# rauch.net
KiCad netlist of a schematic drawn in Altium Designer
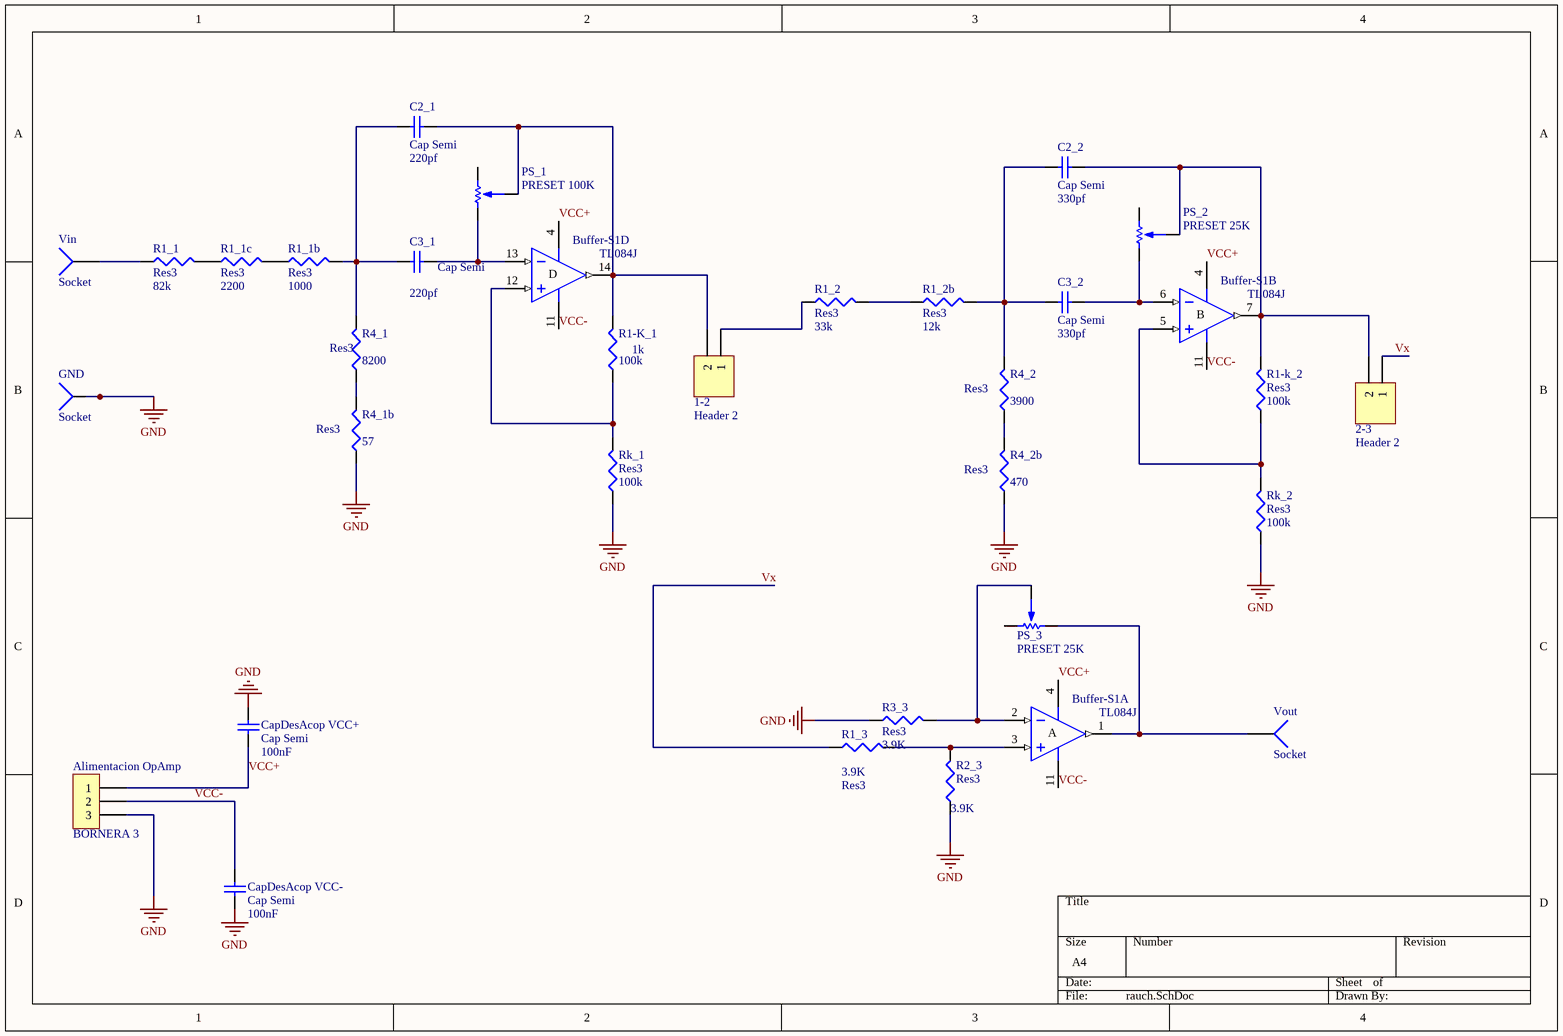
[diagram p0: rauch.SchDoc]

(export (version "E")
  (design (tool "Eeschema 10.0.6"))
  (components
    (comp (ref "1-2")
      (value "Header 2")
      (footprint "HDR1X2")
      (description "Header, 2-Pin")
      (fields (field (name "PUBLISHER") "Altium Limited"))
      (libsource (lib "Miscellaneous Connectors") (part "Header 2"))
    )
    (comp (ref "2-3")
      (value "Header 2")
      (footprint "HDR1X2")
      (description "Header, 2-Pin")
      (fields (field (name "PUBLISHER") "Altium Limited"))
      (libsource (lib "Miscellaneous Connectors") (part "Header 2"))
    )
    (comp (ref "Alimentacion OpAmp")
      (value "BORNERA 3")
      (footprint "BORNERA3")
      (libsource (lib "LIBEBAL") (part "BORNERA 3"))
    )
    (comp (ref "Buffer-S1")
      (value "TL084J")
      (footprint "J014")
      (description "JFET-Input Operational Amplifier")
      (fields (field (name "PUBLISHER") "Altium Limited"))
      (libsource (lib "TI Operational Amplifier") (part "TL084J"))
    )
    (comp (ref "C2_1")
      (value "Cap Semi")
      (footprint "C0805")
      (description "Capacitor (Semiconductor SIM Model)")
      (fields (field (name "ALTIUM_VALUE") "220pf") (field (name "PUBLISHER") "Altium Limited"))
      (libsource (lib "Miscellaneous Devices") (part "Cap Semi"))
    )
    (comp (ref "C2_2")
      (value "Cap Semi")
      (footprint "C0805")
      (description "Capacitor (Semiconductor SIM Model)")
      (fields (field (name "ALTIUM_VALUE") "330pf") (field (name "PUBLISHER") "Altium Limited"))
      (libsource (lib "Miscellaneous Devices") (part "Cap Semi"))
    )
    (comp (ref "C3_1")
      (value "Cap Semi")
      (footprint "C0805")
      (description "Capacitor (Semiconductor SIM Model)")
      (fields (field (name "ALTIUM_VALUE") "220pf") (field (name "PUBLISHER") "Altium Limited"))
      (libsource (lib "Miscellaneous Devices") (part "Cap Semi"))
    )
    (comp (ref "C3_2")
      (value "Cap Semi")
      (footprint "C0805")
      (description "Capacitor (Semiconductor SIM Model)")
      (fields (field (name "ALTIUM_VALUE") "330pf") (field (name "PUBLISHER") "Altium Limited"))
      (libsource (lib "Miscellaneous Devices") (part "Cap Semi"))
    )
    (comp (ref "CapDesAcop VCC+")
      (value "Cap Semi")
      (footprint "C0805")
      (description "Capacitor (Semiconductor SIM Model)")
      (fields (field (name "ALTIUM_VALUE") "100nF") (field (name "PUBLISHER") "Altium Limited"))
      (libsource (lib "Miscellaneous Devices") (part "Cap Semi"))
    )
    (comp (ref "CapDesAcop VCC-")
      (value "Cap Semi")
      (footprint "C0805")
      (description "Capacitor (Semiconductor SIM Model)")
      (fields (field (name "ALTIUM_VALUE") "100nF") (field (name "PUBLISHER") "Altium Limited"))
      (libsource (lib "Miscellaneous Devices") (part "Cap Semi"))
    )
    (comp (ref "GND")
      (value "Socket")
      (footprint "PIN1")
      (fields (field (name "PUBLISHER") "Altium Limited"))
      (libsource (lib "Miscellaneous Connectors") (part "Socket"))
    )
    (comp (ref "PS_1")
      (value "PRESET 100K")
      (footprint "PRESET V")
      (libsource (lib "LIBEBAL") (part "PRESET"))
    )
    (comp (ref "PS_2")
      (value "PRESET 25K")
      (footprint "PRESET V")
      (libsource (lib "LIBEBAL") (part "PRESET"))
    )
    (comp (ref "PS_3")
      (value "PRESET 25K")
      (footprint "PRESET V")
      (libsource (lib "LIBEBAL") (part "PRESET"))
    )
    (comp (ref "R1-K_1")
      (value "1k")
      (footprint "6-0805_M")
      (description "Resistor")
      (fields (field (name "ALTIUM_VALUE") "100k") (field (name "PUBLISHER") "Altium Limited"))
      (libsource (lib "Miscellaneous Devices") (part "Res3"))
    )
    (comp (ref "R1-k_2")
      (value "Res3")
      (footprint "6-0805_M")
      (description "Resistor")
      (fields (field (name "ALTIUM_VALUE") "100k") (field (name "PUBLISHER") "Altium Limited"))
      (libsource (lib "Miscellaneous Devices") (part "Res3"))
    )
    (comp (ref "R1_1")
      (value "Res3")
      (footprint "6-0805_M")
      (description "Resistor")
      (fields (field (name "ALTIUM_VALUE") "82k") (field (name "PUBLISHER") "Altium Limited"))
      (libsource (lib "Miscellaneous Devices") (part "Res3"))
    )
    (comp (ref "R1_1b")
      (value "Res3")
      (footprint "6-0805_M")
      (description "Resistor")
      (fields (field (name "ALTIUM_VALUE") "1000") (field (name "PUBLISHER") "Altium Limited"))
      (libsource (lib "Miscellaneous Devices") (part "Res3"))
    )
    (comp (ref "R1_1c")
      (value "Res3")
      (footprint "6-0805_M")
      (description "Resistor")
      (fields (field (name "ALTIUM_VALUE") "2200") (field (name "PUBLISHER") "Altium Limited"))
      (libsource (lib "Miscellaneous Devices") (part "Res3"))
    )
    (comp (ref "R1_2")
      (value "Res3")
      (footprint "6-0805_M")
      (description "Resistor")
      (fields (field (name "ALTIUM_VALUE") "33k") (field (name "PUBLISHER") "Altium Limited"))
      (libsource (lib "Miscellaneous Devices") (part "Res3"))
    )
    (comp (ref "R1_2b")
      (value "Res3")
      (footprint "6-0805_M")
      (description "Resistor")
      (fields (field (name "ALTIUM_VALUE") "12k") (field (name "PUBLISHER") "Altium Limited"))
      (libsource (lib "Miscellaneous Devices") (part "Res3"))
    )
    (comp (ref "R1_3")
      (value "Res3")
      (footprint "6-0805_M")
      (description "Resistor")
      (fields (field (name "ALTIUM_VALUE") "3.9K") (field (name "PUBLISHER") "Altium Limited"))
      (libsource (lib "Miscellaneous Devices") (part "Res3"))
    )
    (comp (ref "R2_3")
      (value "Res3")
      (footprint "6-0805_M")
      (description "Resistor")
      (fields (field (name "ALTIUM_VALUE") "3.9K") (field (name "PUBLISHER") "Altium Limited"))
      (libsource (lib "Miscellaneous Devices") (part "Res3"))
    )
    (comp (ref "R3_3")
      (value "Res3")
      (footprint "6-0805_M")
      (description "Resistor")
      (fields (field (name "ALTIUM_VALUE") "3.9K") (field (name "PUBLISHER") "Altium Limited"))
      (libsource (lib "Miscellaneous Devices") (part "Res3"))
    )
    (comp (ref "R4_1")
      (value "Res3")
      (footprint "6-0805_M")
      (description "Resistor")
      (fields (field (name "ALTIUM_VALUE") "8200") (field (name "PUBLISHER") "Altium Limited"))
      (libsource (lib "Miscellaneous Devices") (part "Res3"))
    )
    (comp (ref "R4_1b")
      (value "Res3")
      (footprint "6-0805_M")
      (description "Resistor")
      (fields (field (name "ALTIUM_VALUE") "57") (field (name "PUBLISHER") "Altium Limited"))
      (libsource (lib "Miscellaneous Devices") (part "Res3"))
    )
    (comp (ref "R4_2")
      (value "Res3")
      (footprint "6-0805_M")
      (description "Resistor")
      (fields (field (name "ALTIUM_VALUE") "3900") (field (name "PUBLISHER") "Altium Limited"))
      (libsource (lib "Miscellaneous Devices") (part "Res3"))
    )
    (comp (ref "R4_2b")
      (value "Res3")
      (footprint "6-0805_M")
      (description "Resistor")
      (fields (field (name "ALTIUM_VALUE") "470") (field (name "PUBLISHER") "Altium Limited"))
      (libsource (lib "Miscellaneous Devices") (part "Res3"))
    )
    (comp (ref "Rk_1")
      (value "Res3")
      (footprint "6-0805_M")
      (description "Resistor")
      (fields (field (name "ALTIUM_VALUE") "100k") (field (name "PUBLISHER") "Altium Limited"))
      (libsource (lib "Miscellaneous Devices") (part "Res3"))
    )
    (comp (ref "Rk_2")
      (value "Res3")
      (footprint "6-0805_M")
      (description "Resistor")
      (fields (field (name "ALTIUM_VALUE") "100k") (field (name "PUBLISHER") "Altium Limited"))
      (libsource (lib "Miscellaneous Devices") (part "Res3"))
    )
    (comp (ref "Vin")
      (value "Socket")
      (footprint "PIN1")
      (fields (field (name "PUBLISHER") "Altium Limited"))
      (libsource (lib "Miscellaneous Connectors") (part "Socket"))
    )
    (comp (ref "Vout")
      (value "Socket")
      (footprint "PIN1")
      (fields (field (name "PUBLISHER") "Altium Limited"))
      (libsource (lib "Miscellaneous Connectors") (part "Socket"))
    )
  )
  (nets
    (net (code "1") (name "/VCC+") (class "Default")
      (node (ref "Alimentacion OpAmp") (pin "1") (pinfunction "1_1") (pintype "passive"))
      (node (ref "Buffer-S1") (pin "4") (pinfunction "V+_4") (pintype "power_in"))
      (node (ref "CapDesAcop VCC+") (pin "2") (pinfunction "2_2") (pintype "passive"))
    )
    (net (code "2") (name "/VCC-") (class "Default")
      (node (ref "Alimentacion OpAmp") (pin "2") (pinfunction "2_2") (pintype "passive"))
      (node (ref "Buffer-S1") (pin "11") (pinfunction "V-_11") (pintype "power_in"))
      (node (ref "CapDesAcop VCC-") (pin "2") (pinfunction "2_2") (pintype "passive"))
    )
    (net (code "3") (name "/Vx") (class "Default")
      (node (ref "2-3") (pin "1") (pinfunction "1_1") (pintype "passive"))
      (node (ref "R1_3") (pin "1") (pinfunction "1_1") (pintype "passive"))
    )
    (net (code "4") (name "GND") (class "Default")
      (node (ref "Alimentacion OpAmp") (pin "3") (pinfunction "3_3") (pintype "passive"))
      (node (ref "CapDesAcop VCC+") (pin "1") (pinfunction "1_1") (pintype "passive"))
      (node (ref "CapDesAcop VCC-") (pin "1") (pinfunction "1_1") (pintype "passive"))
      (node (ref "GND") (pin "1") (pinfunction "1_1") (pintype "passive"))
      (node (ref "R2_3") (pin "1") (pinfunction "1_1") (pintype "passive"))
      (node (ref "R3_3") (pin "1") (pinfunction "1_1") (pintype "passive"))
      (node (ref "R4_1b") (pin "1") (pinfunction "1_1") (pintype "passive"))
      (node (ref "R4_2b") (pin "1") (pinfunction "1_1") (pintype "passive"))
      (node (ref "Rk_1") (pin "1") (pinfunction "1_1") (pintype "passive"))
      (node (ref "Rk_2") (pin "1") (pinfunction "1_1") (pintype "passive"))
    )
    (net (code "5") (name "Net-(1-2-Pad1)") (class "Default")
      (node (ref "1-2") (pin "1") (pinfunction "1_1") (pintype "passive"))
      (node (ref "R1_2") (pin "1") (pinfunction "1_1") (pintype "passive"))
    )
    (net (code "6") (name "Net-(Buffer-S1A-IN+)") (class "Default")
      (node (ref "Buffer-S1") (pin "3") (pinfunction "IN+_3") (pintype "input"))
      (node (ref "R1_3") (pin "2") (pinfunction "2_2") (pintype "passive"))
      (node (ref "R2_3") (pin "2") (pinfunction "2_2") (pintype "passive"))
    )
    (net (code "7") (name "Net-(Buffer-S1A-IN-)") (class "Default")
      (node (ref "Buffer-S1") (pin "2") (pinfunction "IN-_2") (pintype "input"))
      (node (ref "PS_3") (pin "2") (pinfunction "2_2") (pintype "passive"))
      (node (ref "R3_3") (pin "2") (pinfunction "2_2") (pintype "passive"))
    )
    (net (code "8") (name "Net-(Buffer-S1A-OUT)") (class "Default")
      (node (ref "Buffer-S1") (pin "1") (pinfunction "OUT_1") (pintype "output"))
      (node (ref "PS_3") (pin "3") (pinfunction "3_3") (pintype "passive"))
      (node (ref "Vout") (pin "1") (pinfunction "1_1") (pintype "passive"))
    )
    (net (code "9") (name "Net-(Buffer-S1B-IN+)") (class "Default")
      (node (ref "Buffer-S1") (pin "5") (pinfunction "IN+_5") (pintype "input"))
      (node (ref "R1-k_2") (pin "1") (pinfunction "1_1") (pintype "passive"))
      (node (ref "Rk_2") (pin "2") (pinfunction "2_2") (pintype "passive"))
    )
    (net (code "10") (name "Net-(Buffer-S1B-IN-)") (class "Default")
      (node (ref "Buffer-S1") (pin "6") (pinfunction "IN-_6") (pintype "input"))
      (node (ref "C3_2") (pin "1") (pinfunction "1_1") (pintype "passive"))
      (node (ref "PS_2") (pin "3") (pinfunction "3_3") (pintype "passive"))
    )
    (net (code "11") (name "Net-(Buffer-S1B-OUT)") (class "Default")
      (node (ref "2-3") (pin "2") (pinfunction "2_2") (pintype "passive"))
      (node (ref "Buffer-S1") (pin "7") (pinfunction "OUT_7") (pintype "output"))
      (node (ref "C2_2") (pin "1") (pinfunction "1_1") (pintype "passive"))
      (node (ref "PS_2") (pin "2") (pinfunction "2_2") (pintype "passive"))
      (node (ref "R1-k_2") (pin "2") (pinfunction "2_2") (pintype "passive"))
    )
    (net (code "12") (name "Net-(Buffer-S1D-IN+)") (class "Default")
      (node (ref "Buffer-S1") (pin "12") (pinfunction "IN+_12") (pintype "input"))
      (node (ref "R1-K_1") (pin "1") (pinfunction "1_1") (pintype "passive"))
      (node (ref "Rk_1") (pin "2") (pinfunction "2_2") (pintype "passive"))
    )
    (net (code "13") (name "Net-(Buffer-S1D-IN-)") (class "Default")
      (node (ref "Buffer-S1") (pin "13") (pinfunction "IN-_13") (pintype "input"))
      (node (ref "C3_1") (pin "1") (pinfunction "1_1") (pintype "passive"))
      (node (ref "PS_1") (pin "3") (pinfunction "3_3") (pintype "passive"))
    )
    (net (code "14") (name "Net-(Buffer-S1D-OUT)") (class "Default")
      (node (ref "1-2") (pin "2") (pinfunction "2_2") (pintype "passive"))
      (node (ref "Buffer-S1") (pin "14") (pinfunction "OUT_14") (pintype "output"))
      (node (ref "C2_1") (pin "1") (pinfunction "1_1") (pintype "passive"))
      (node (ref "PS_1") (pin "2") (pinfunction "2_2") (pintype "passive"))
      (node (ref "R1-K_1") (pin "2") (pinfunction "2_2") (pintype "passive"))
    )
    (net (code "15") (name "Net-(C2_1-Pad2)") (class "Default")
      (node (ref "C2_1") (pin "2") (pinfunction "2_2") (pintype "passive"))
      (node (ref "C3_1") (pin "2") (pinfunction "2_2") (pintype "passive"))
      (node (ref "R1_1b") (pin "2") (pinfunction "2_2") (pintype "passive"))
      (node (ref "R4_1") (pin "2") (pinfunction "2_2") (pintype "passive"))
    )
    (net (code "16") (name "Net-(C2_2-Pad2)") (class "Default")
      (node (ref "C2_2") (pin "2") (pinfunction "2_2") (pintype "passive"))
      (node (ref "C3_2") (pin "2") (pinfunction "2_2") (pintype "passive"))
      (node (ref "R1_2b") (pin "2") (pinfunction "2_2") (pintype "passive"))
      (node (ref "R4_2") (pin "2") (pinfunction "2_2") (pintype "passive"))
    )
    (net (code "17") (name "Net-(R1_1-Pad1)") (class "Default")
      (node (ref "R1_1") (pin "1") (pinfunction "1_1") (pintype "passive"))
      (node (ref "Vin") (pin "1") (pinfunction "1_1") (pintype "passive"))
    )
    (net (code "18") (name "Net-(R1_1-Pad2)") (class "Default")
      (node (ref "R1_1") (pin "2") (pinfunction "2_2") (pintype "passive"))
      (node (ref "R1_1c") (pin "1") (pinfunction "1_1") (pintype "passive"))
    )
    (net (code "19") (name "Net-(R1_1b-Pad1)") (class "Default")
      (node (ref "R1_1b") (pin "1") (pinfunction "1_1") (pintype "passive"))
      (node (ref "R1_1c") (pin "2") (pinfunction "2_2") (pintype "passive"))
    )
    (net (code "20") (name "Net-(R1_2-Pad2)") (class "Default")
      (node (ref "R1_2") (pin "2") (pinfunction "2_2") (pintype "passive"))
      (node (ref "R1_2b") (pin "1") (pinfunction "1_1") (pintype "passive"))
    )
    (net (code "21") (name "Net-(R4_1-Pad1)") (class "Default")
      (node (ref "R4_1") (pin "1") (pinfunction "1_1") (pintype "passive"))
      (node (ref "R4_1b") (pin "2") (pinfunction "2_2") (pintype "passive"))
    )
    (net (code "22") (name "Net-(R4_2-Pad1)") (class "Default")
      (node (ref "R4_2") (pin "1") (pinfunction "1_1") (pintype "passive"))
      (node (ref "R4_2b") (pin "2") (pinfunction "2_2") (pintype "passive"))
    )
    (net (code "23") (name "unconnected-(PS_1-Pad1)") (class "Default")
      (node (ref "PS_1") (pin "1") (pinfunction "1_1") (pintype "passive"))
    )
    (net (code "24") (name "unconnected-(PS_2-Pad1)") (class "Default")
      (node (ref "PS_2") (pin "1") (pinfunction "1_1") (pintype "passive"))
    )
    (net (code "25") (name "unconnected-(PS_3-Pad1)") (class "Default")
      (node (ref "PS_3") (pin "1") (pinfunction "1_1") (pintype "passive"))
    )
  )
)
